# Oasis_Heater_Testing.net
KiCad netlist of a schematic drawn in Altium Designer
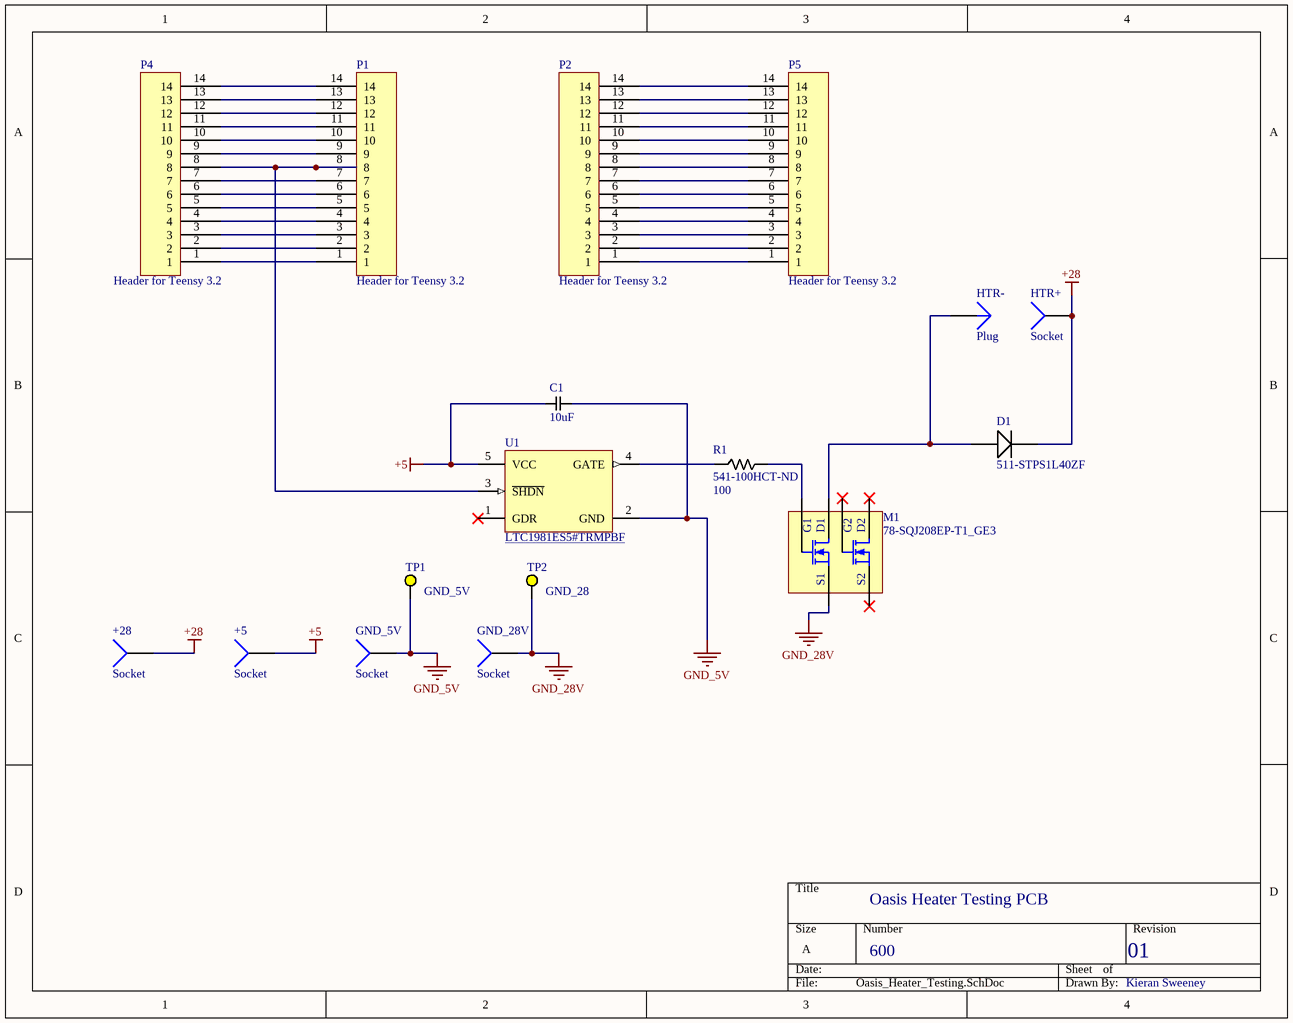
[diagram p0: Oasis_Heater_Testing.SchDoc]

(export (version "E")
  (design (tool "Eeschema 10.0.6"))
  (components
    (comp (ref "+5")
      (value "Socket")
      (footprint "PIN1")
      (fields (field (name "PUBLISHER") "Altium Limited"))
      (libsource (lib "Miscellaneous Connectors") (part "Socket"))
    )
    (comp (ref "+28")
      (value "Socket")
      (footprint "PIN1")
      (fields (field (name "PUBLISHER") "Altium Limited"))
      (libsource (lib "Miscellaneous Connectors") (part "Socket"))
    )
    (comp (ref "C1")
      (value "10uF")
      (footprint "IMPERIAL0805_CAPACITOR")
      (description "10 uF Capacitor")
      (fields (field (name "Comment") "10uF Capacitor"))
      (libsource (lib "Oasis_Heater_Testing") (part "C2012X8L1A106K125AE"))
    )
    (comp (ref "D1")
      (value "STPS1L40ZF")
      (footprint "*SODFL3718X108N")
      (description "1A Schottky Diode")
      (fields (field (name "SUPPLIER PART NUMBER 1") "511-STPS1L40ZF"))
      (libsource (lib "Oasis_Heater_Testing") (part "STPS1L40ZF"))
    )
    (comp (ref "GND_5V")
      (value "Socket")
      (footprint "PIN1")
      (fields (field (name "PUBLISHER") "Altium Limited"))
      (libsource (lib "Miscellaneous Connectors") (part "Socket"))
    )
    (comp (ref "GND_28V")
      (value "Socket")
      (footprint "PIN1")
      (fields (field (name "PUBLISHER") "Altium Limited"))
      (libsource (lib "Miscellaneous Connectors") (part "Socket"))
    )
    (comp (ref "HTR+")
      (value "Socket")
      (footprint "PIN1")
      (fields (field (name "PUBLISHER") "Altium Limited"))
      (libsource (lib "Miscellaneous Connectors") (part "Socket"))
    )
    (comp (ref "HTR-")
      (value "Plug")
      (footprint "PIN1")
      (fields (field (name "PUBLISHER") "Altium Limited"))
      (libsource (lib "Miscellaneous Connectors") (part "Plug"))
    )
    (comp (ref "M1")
      (value "NPN MOSFET")
      (footprint "PowerPAK SO-8L DUAL ASYMMETRIC")
      (description "Two NPN Power Transistors for heater power control")
      (fields (field (name "SUPPLIER PART NUMBER 1") "78-SQJ208EP-T1_GE3"))
      (libsource (lib "Oasis_Heater_Testing") (part "SQJ208EP-T1_GE3"))
    )
    (comp (ref "P1")
      (value "Header for Teensy 3.2")
      (footprint "BL114G")
      (description "14-pin header, to be used with Teensy 3.2")
      (libsource (lib "Oasis_Heater_Testing") (part "BL114G"))
    )
    (comp (ref "P2")
      (value "Header for Teensy 3.2")
      (footprint "BL114G")
      (description "14-pin header, to be used with Teensy 3.2")
      (libsource (lib "") (part "BL114G_1"))
    )
    (comp (ref "P4")
      (value "Header for Teensy 3.2")
      (footprint "BL114G")
      (description "14-pin header, to be used with Teensy 3.2")
      (libsource (lib "") (part "BL114G_1"))
    )
    (comp (ref "P5")
      (value "Header for Teensy 3.2")
      (footprint "BL114G")
      (description "14-pin header, to be used with Teensy 3.2")
      (libsource (lib "Oasis_Heater_Testing") (part "BL114G"))
    )
    (comp (ref "R1")
      (value "100")
      (footprint "Imperial0603_RES")
      (description "100 Ohm Resistor")
      (fields
        (field (name "SUPPLIER PART NUMBER 1") "541-100HCT-ND")
        (field (name "Comment") "CRCW0603100RFKEAC")
      )
      (libsource (lib "Oasis_Heater_Testing") (part "CRCW0603100RFKEAC"))
    )
    (comp (ref "TP1")
      (value "GND_5V")
      (footprint "KSTN-5004")
      (description "Test Point, Yellow, 1-Pin THD, RoHS, Bulk")
      (fields (field (name "MANUFACTURER") "Keystone"))
      (libsource (lib "Altium Content Vault") (part "KSTN-TP-5004"))
    )
    (comp (ref "TP2")
      (value "GND_28")
      (footprint "KSTN-5004")
      (description "Test Point, Yellow, 1-Pin THD, RoHS, Bulk")
      (fields (field (name "MANUFACTURER") "Keystone"))
      (libsource (lib "Altium Content Vault") (part "KSTN-TP-5004"))
    )
    (comp (ref "U1")
      (value "LTC1981ES5#TRMPBF")
      (footprint "LT-S5-5-SOT-23_N")
      (fields (field (name "MANUFACTURER") "Linear Technology"))
      (libsource (lib "Altium Content Vault") (part "LT-LTC1981-S5-5"))
    )
  )
  (nets
    (net (code "1") (name "+5") (class "Default")
      (node (ref "+5") (pin "1") (pinfunction "1_1") (pintype "passive"))
      (node (ref "C1") (pin "1") (pinfunction "1_1") (pintype "passive"))
      (node (ref "U1") (pin "5") (pinfunction "VCC_5") (pintype "power_in"))
    )
    (net (code "2") (name "+28") (class "Default")
      (node (ref "+28") (pin "1") (pinfunction "1_1") (pintype "passive"))
      (node (ref "D1") (pin "1") (pinfunction "cathode_1") (pintype "passive"))
      (node (ref "HTR+") (pin "1") (pinfunction "1_1") (pintype "passive"))
    )
    (net (code "3") (name "GND_5V") (class "Default")
      (node (ref "C1") (pin "2") (pinfunction "2_2") (pintype "passive"))
      (node (ref "GND_5V") (pin "1") (pinfunction "1_1") (pintype "passive"))
      (node (ref "TP1") (pin "1") (pinfunction "1_1") (pintype "passive"))
      (node (ref "U1") (pin "2") (pinfunction "GND_2") (pintype "power_in"))
    )
    (net (code "4") (name "GND_28V") (class "Default")
      (node (ref "GND_28V") (pin "1") (pinfunction "1_1") (pintype "passive"))
      (node (ref "M1") (pin "1") (pinfunction "S1_1") (pintype "passive"))
      (node (ref "TP2") (pin "1") (pinfunction "1_1") (pintype "passive"))
    )
    (net (code "5") (name "Net-(D1-anode)") (class "Default")
      (node (ref "D1") (pin "2") (pinfunction "anode_2") (pintype "passive"))
      (node (ref "HTR-") (pin "1") (pinfunction "1_1") (pintype "passive"))
      (node (ref "M1") (pin "5") (pinfunction "D1_5") (pintype "passive"))
    )
    (net (code "6") (name "Net-(M1-G1)") (class "Default")
      (node (ref "M1") (pin "2") (pinfunction "G1_2") (pintype "passive"))
      (node (ref "R1") (pin "1") (pinfunction "1_1") (pintype "passive"))
    )
    (net (code "7") (name "Net-(P1-Pad1)") (class "Default")
      (node (ref "P1") (pin "1") (pinfunction "1_1") (pintype "passive"))
      (node (ref "P4") (pin "1") (pinfunction "1_1") (pintype "passive"))
    )
    (net (code "8") (name "Net-(P1-Pad2)") (class "Default")
      (node (ref "P1") (pin "2") (pinfunction "2_2") (pintype "passive"))
      (node (ref "P4") (pin "2") (pinfunction "2_2") (pintype "passive"))
    )
    (net (code "9") (name "Net-(P1-Pad3)") (class "Default")
      (node (ref "P1") (pin "3") (pinfunction "3_3") (pintype "passive"))
      (node (ref "P4") (pin "3") (pinfunction "3_3") (pintype "passive"))
    )
    (net (code "10") (name "Net-(P1-Pad4)") (class "Default")
      (node (ref "P1") (pin "4") (pinfunction "4_4") (pintype "passive"))
      (node (ref "P4") (pin "4") (pinfunction "4_4") (pintype "passive"))
    )
    (net (code "11") (name "Net-(P1-Pad5)") (class "Default")
      (node (ref "P1") (pin "5") (pinfunction "5_5") (pintype "passive"))
      (node (ref "P4") (pin "5") (pinfunction "5_5") (pintype "passive"))
    )
    (net (code "12") (name "Net-(P1-Pad6)") (class "Default")
      (node (ref "P1") (pin "6") (pinfunction "6_6") (pintype "passive"))
      (node (ref "P4") (pin "6") (pinfunction "6_6") (pintype "passive"))
    )
    (net (code "13") (name "Net-(P1-Pad7)") (class "Default")
      (node (ref "P1") (pin "7") (pinfunction "7_7") (pintype "passive"))
      (node (ref "P4") (pin "7") (pinfunction "7_7") (pintype "passive"))
    )
    (net (code "14") (name "Net-(P1-Pad9)") (class "Default")
      (node (ref "P1") (pin "9") (pinfunction "9_9") (pintype "passive"))
      (node (ref "P4") (pin "9") (pinfunction "9_9") (pintype "passive"))
    )
    (net (code "15") (name "Net-(P1-Pad10)") (class "Default")
      (node (ref "P1") (pin "10") (pinfunction "10_10") (pintype "passive"))
      (node (ref "P4") (pin "10") (pinfunction "10_10") (pintype "passive"))
    )
    (net (code "16") (name "Net-(P1-Pad11)") (class "Default")
      (node (ref "P1") (pin "11") (pinfunction "11_11") (pintype "passive"))
      (node (ref "P4") (pin "11") (pinfunction "11_11") (pintype "passive"))
    )
    (net (code "17") (name "Net-(P1-Pad12)") (class "Default")
      (node (ref "P1") (pin "12") (pinfunction "12_12") (pintype "passive"))
      (node (ref "P4") (pin "12") (pinfunction "12_12") (pintype "passive"))
    )
    (net (code "18") (name "Net-(P1-Pad13)") (class "Default")
      (node (ref "P1") (pin "13") (pinfunction "13_13") (pintype "passive"))
      (node (ref "P4") (pin "13") (pinfunction "13_13") (pintype "passive"))
    )
    (net (code "19") (name "Net-(P1-Pad14)") (class "Default")
      (node (ref "P1") (pin "14") (pinfunction "14_14") (pintype "passive"))
      (node (ref "P4") (pin "14") (pinfunction "14_14") (pintype "passive"))
    )
    (net (code "20") (name "Net-(P2-Pad1)") (class "Default")
      (node (ref "P2") (pin "1") (pinfunction "1_1") (pintype "passive"))
      (node (ref "P5") (pin "1") (pinfunction "1_1") (pintype "passive"))
    )
    (net (code "21") (name "Net-(P2-Pad2)") (class "Default")
      (node (ref "P2") (pin "2") (pinfunction "2_2") (pintype "passive"))
      (node (ref "P5") (pin "2") (pinfunction "2_2") (pintype "passive"))
    )
    (net (code "22") (name "Net-(P2-Pad3)") (class "Default")
      (node (ref "P2") (pin "3") (pinfunction "3_3") (pintype "passive"))
      (node (ref "P5") (pin "3") (pinfunction "3_3") (pintype "passive"))
    )
    (net (code "23") (name "Net-(P2-Pad4)") (class "Default")
      (node (ref "P2") (pin "4") (pinfunction "4_4") (pintype "passive"))
      (node (ref "P5") (pin "4") (pinfunction "4_4") (pintype "passive"))
    )
    (net (code "24") (name "Net-(P2-Pad5)") (class "Default")
      (node (ref "P2") (pin "5") (pinfunction "5_5") (pintype "passive"))
      (node (ref "P5") (pin "5") (pinfunction "5_5") (pintype "passive"))
    )
    (net (code "25") (name "Net-(P2-Pad6)") (class "Default")
      (node (ref "P2") (pin "6") (pinfunction "6_6") (pintype "passive"))
      (node (ref "P5") (pin "6") (pinfunction "6_6") (pintype "passive"))
    )
    (net (code "26") (name "Net-(P2-Pad7)") (class "Default")
      (node (ref "P2") (pin "7") (pinfunction "7_7") (pintype "passive"))
      (node (ref "P5") (pin "7") (pinfunction "7_7") (pintype "passive"))
    )
    (net (code "27") (name "Net-(P2-Pad8)") (class "Default")
      (node (ref "P2") (pin "8") (pinfunction "8_8") (pintype "passive"))
      (node (ref "P5") (pin "8") (pinfunction "8_8") (pintype "passive"))
    )
    (net (code "28") (name "Net-(P2-Pad9)") (class "Default")
      (node (ref "P2") (pin "9") (pinfunction "9_9") (pintype "passive"))
      (node (ref "P5") (pin "9") (pinfunction "9_9") (pintype "passive"))
    )
    (net (code "29") (name "Net-(P2-Pad10)") (class "Default")
      (node (ref "P2") (pin "10") (pinfunction "10_10") (pintype "passive"))
      (node (ref "P5") (pin "10") (pinfunction "10_10") (pintype "passive"))
    )
    (net (code "30") (name "Net-(P2-Pad11)") (class "Default")
      (node (ref "P2") (pin "11") (pinfunction "11_11") (pintype "passive"))
      (node (ref "P5") (pin "11") (pinfunction "11_11") (pintype "passive"))
    )
    (net (code "31") (name "Net-(P2-Pad12)") (class "Default")
      (node (ref "P2") (pin "12") (pinfunction "12_12") (pintype "passive"))
      (node (ref "P5") (pin "12") (pinfunction "12_12") (pintype "passive"))
    )
    (net (code "32") (name "Net-(P2-Pad13)") (class "Default")
      (node (ref "P2") (pin "13") (pinfunction "13_13") (pintype "passive"))
      (node (ref "P5") (pin "13") (pinfunction "13_13") (pintype "passive"))
    )
    (net (code "33") (name "Net-(P2-Pad14)") (class "Default")
      (node (ref "P2") (pin "14") (pinfunction "14_14") (pintype "passive"))
      (node (ref "P5") (pin "14") (pinfunction "14_14") (pintype "passive"))
    )
    (net (code "34") (name "Net-(U1-GATE)") (class "Default")
      (node (ref "R1") (pin "2") (pinfunction "2_2") (pintype "passive"))
      (node (ref "U1") (pin "4") (pinfunction "GATE_4") (pintype "output"))
    )
    (net (code "35") (name "Net-(U1-~{SHDN})") (class "Default")
      (node (ref "P1") (pin "8") (pinfunction "8_8") (pintype "passive"))
      (node (ref "P4") (pin "8") (pinfunction "8_8") (pintype "passive"))
      (node (ref "U1") (pin "3") (pinfunction "~{SHDN}_3") (pintype "input"))
    )
    (net (code "36") (name "unconnected-(M1-D2-Pad6)") (class "Default")
      (node (ref "M1") (pin "6") (pinfunction "D2_6") (pintype "passive+no_connect"))
    )
    (net (code "37") (name "unconnected-(M1-G2-Pad4)") (class "Default")
      (node (ref "M1") (pin "4") (pinfunction "G2_4") (pintype "passive+no_connect"))
    )
    (net (code "38") (name "unconnected-(M1-S2-Pad3)") (class "Default")
      (node (ref "M1") (pin "3") (pinfunction "S2_3") (pintype "passive+no_connect"))
    )
    (net (code "39") (name "unconnected-(U1-GDR-Pad1)") (class "Default")
      (node (ref "U1") (pin "1") (pinfunction "GDR_1") (pintype "open_collector+no_connect"))
    )
  )
)
